# Shield-v1_4.net
KiCad netlist of a schematic drawn in EAGLE
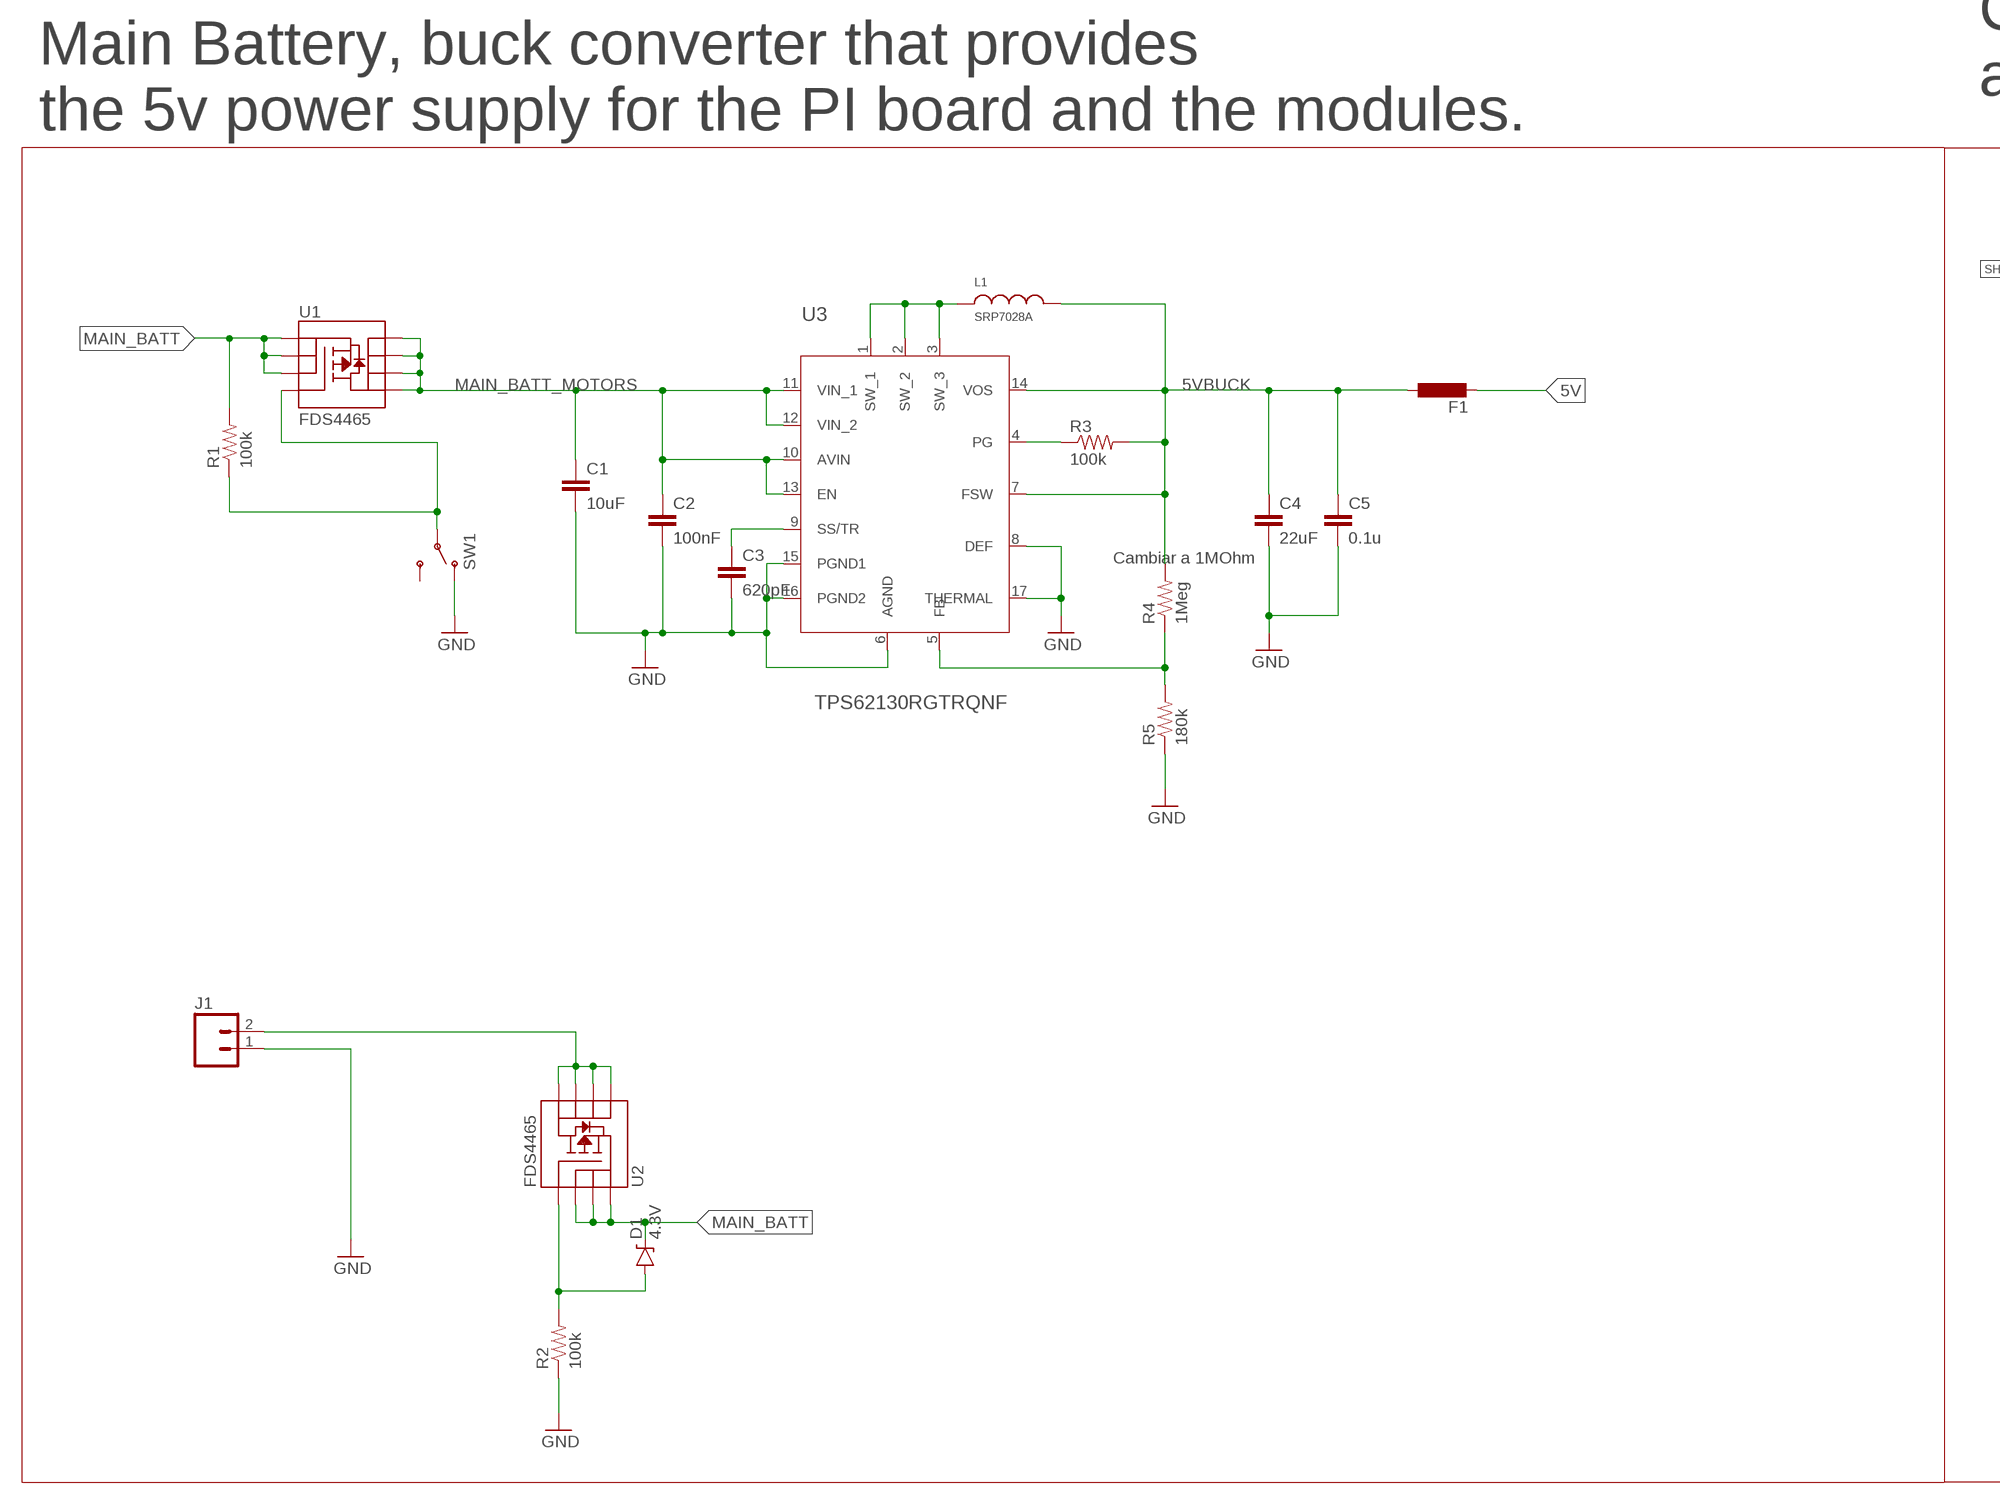
[diagram p0: schematic, sheet 1, part 1 of 2]
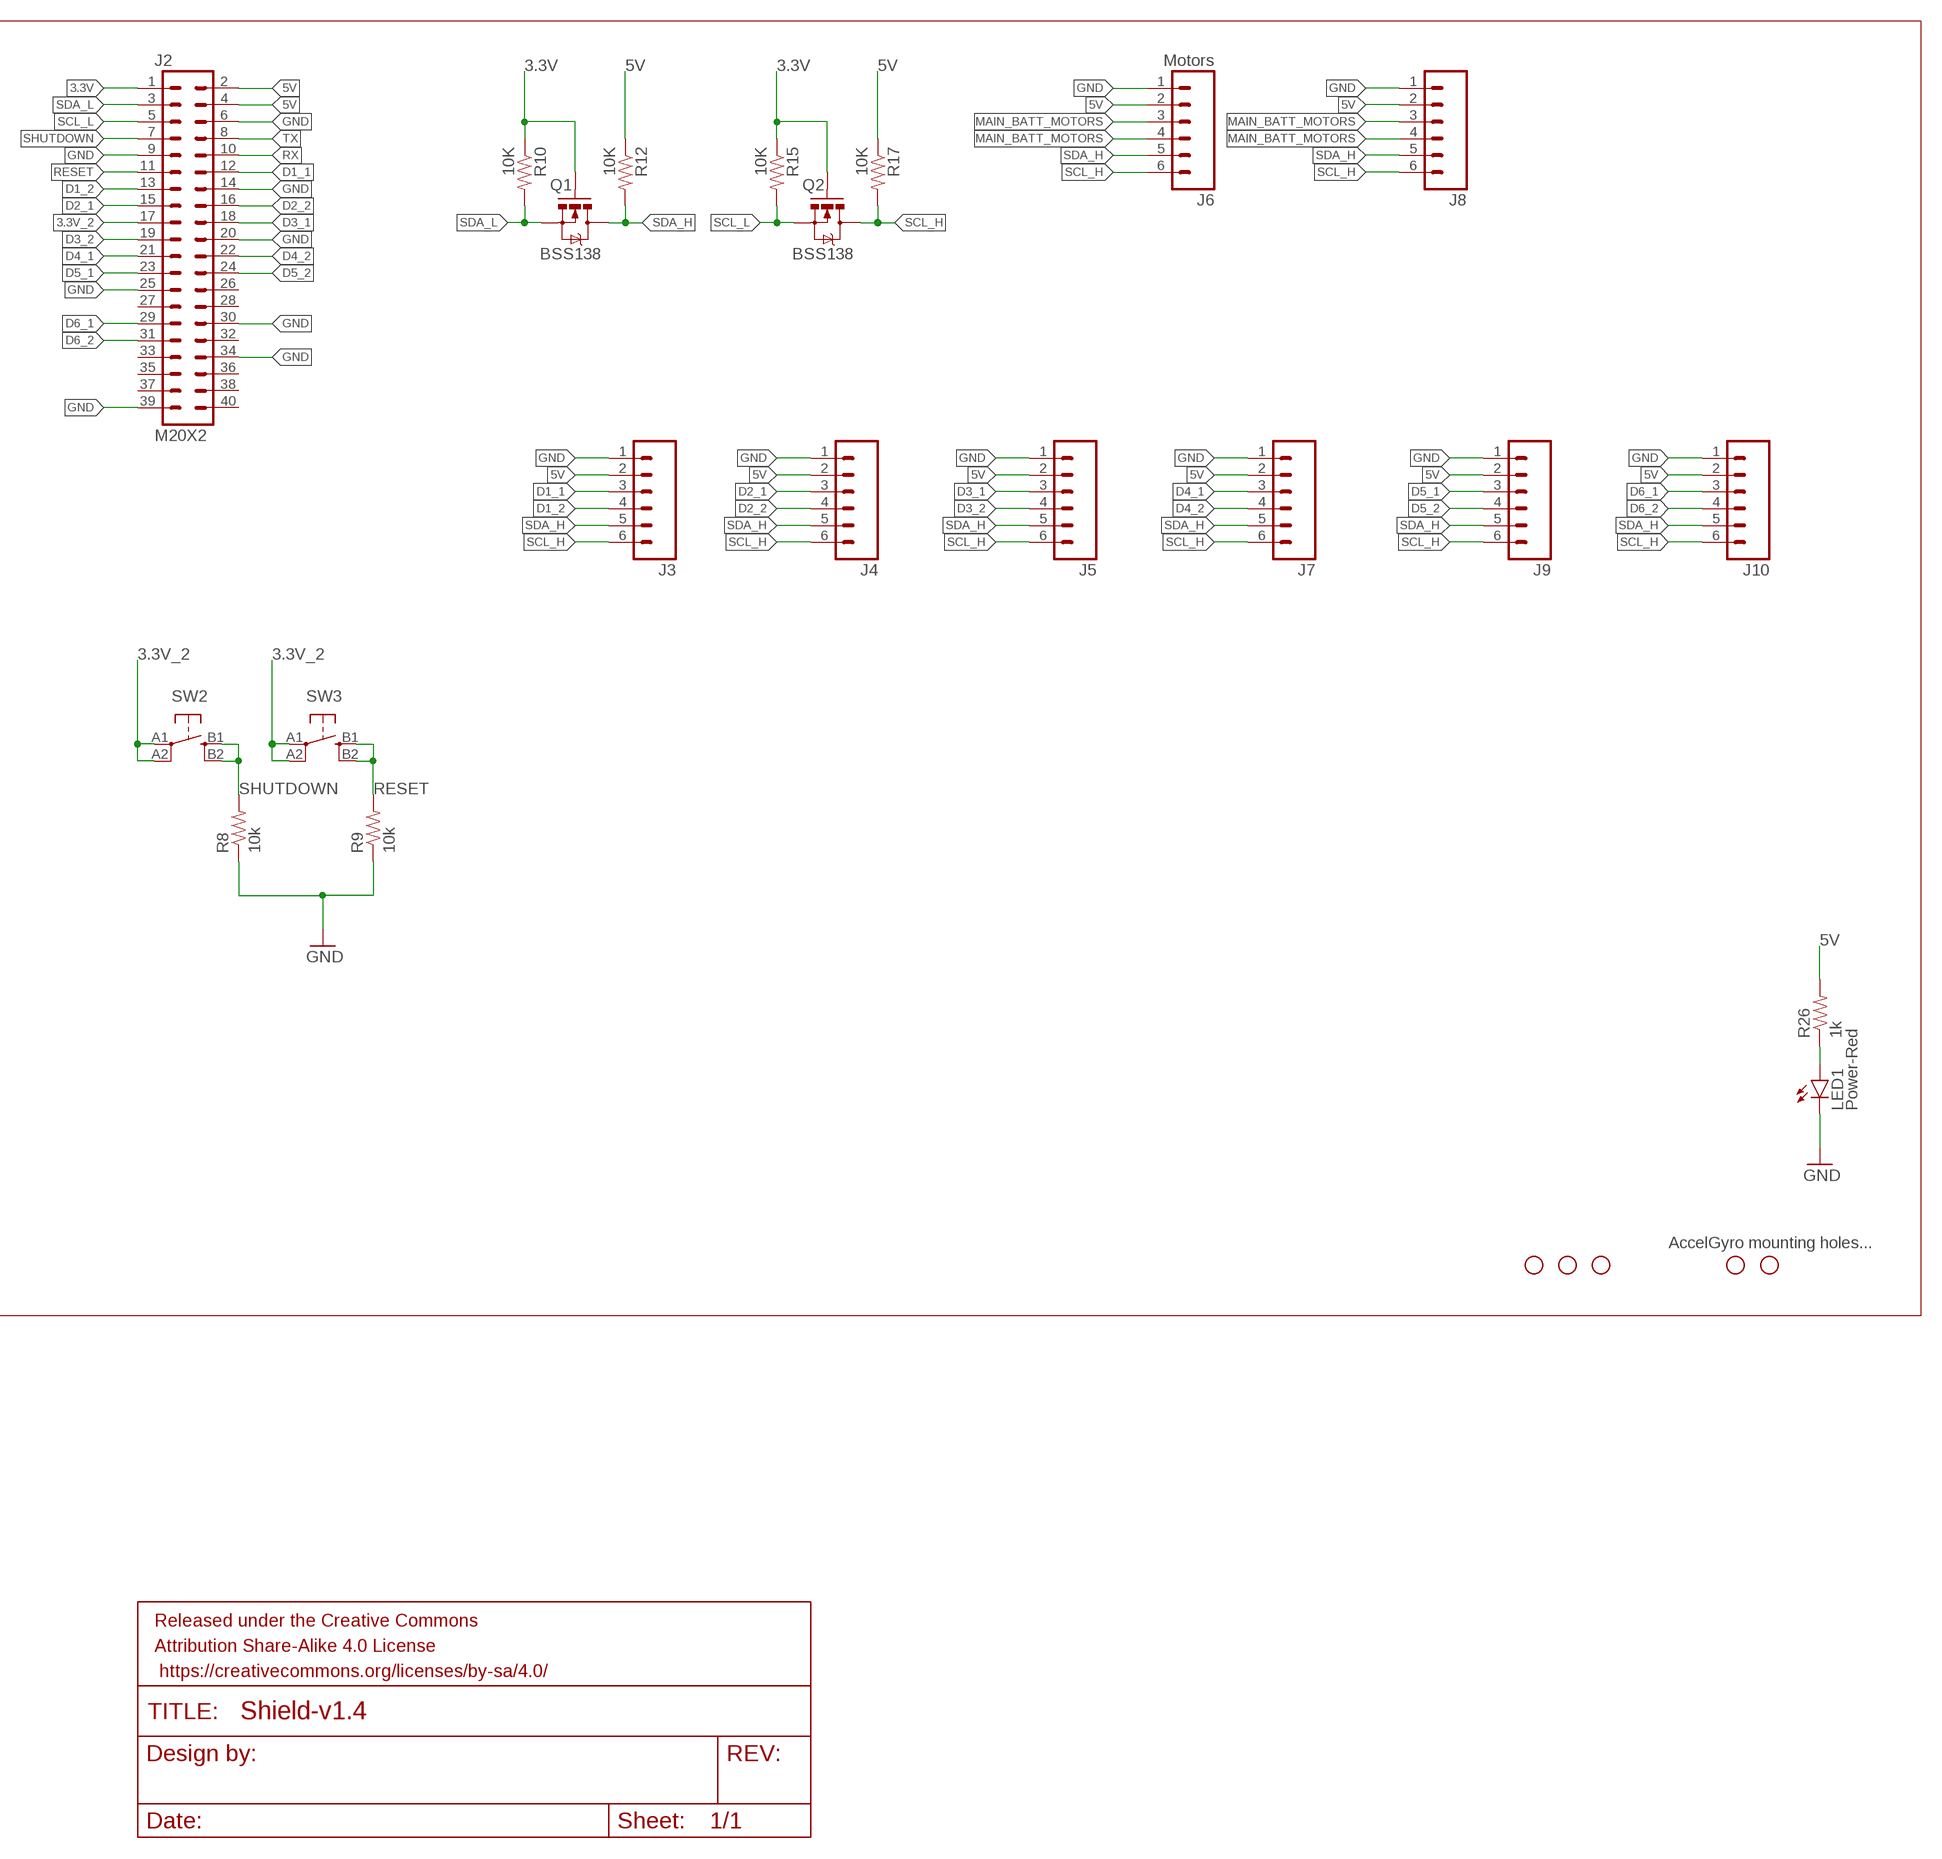
[diagram p1: schematic, sheet 1, part 2 of 2]

(export (version "E")
  (design (tool "Eeschema 10.0.6"))
  (components
    (comp (ref "C1")
      (value "10uF")
      (footprint "eagle-import:0603-CAP")
      (libsource (lib "eagle-import") (part "CAP0603-CAP"))
    )
    (comp (ref "C2")
      (value "100nF")
      (footprint "eagle-import:0603-CAP")
      (libsource (lib "eagle-import") (part "CAP0603-CAP"))
    )
    (comp (ref "C3")
      (value "620pF")
      (footprint "eagle-import:0603-CAP")
      (libsource (lib "eagle-import") (part "CAP0603-CAP"))
    )
    (comp (ref "C4")
      (value "22uF")
      (footprint "eagle-import:0805")
      (libsource (lib "eagle-import") (part "SparkFun-Passives_CAP0805"))
    )
    (comp (ref "C5")
      (value "0.1u")
      (footprint "eagle-import:0603-CAP")
      (libsource (lib "eagle-import") (part "CAP0603-CAP"))
    )
    (comp (ref "D1")
      (value "4.3V")
      (footprint "eagle-import:SOD-323")
      (libsource (lib "eagle-import") (part "DIODE-ZENER3.3V"))
    )
    (comp (ref "F1")
      (value "L-EUL1812")
      (footprint "eagle-import:L1812")
      (libsource (lib "eagle-import") (part "L-EUL1812"))
    )
    (comp (ref "FRAME1")
      (value "FRAME-LETTERNO_PACKAGE")
      (footprint "eagle-import:DUMMY")
      (fields (field (name "DESIGNER") "Nobody"))
      (libsource (lib "eagle-import") (part "FRAME-LETTERNO_PACKAGE"))
    )
    (comp (ref "H1")
      (value "STAND-OFFPLATED")
      (footprint "eagle-import:STAND-OFF-PLATED")
      (libsource (lib "eagle-import") (part "STAND-OFFPLATED"))
    )
    (comp (ref "H2")
      (value "STAND-OFFPLATED")
      (footprint "eagle-import:STAND-OFF-PLATED")
      (libsource (lib "eagle-import") (part "STAND-OFFPLATED"))
    )
    (comp (ref "H3")
      (value "STAND-OFFNORMAL")
      (footprint "eagle-import:STAND-OFF")
      (libsource (lib "eagle-import") (part "STAND-OFFNORMAL"))
    )
    (comp (ref "H4")
      (value "STAND-OFF")
      (footprint "eagle-import:STAND-OFF")
      (libsource (lib "eagle-import") (part "STAND-OFF"))
    )
    (comp (ref "H5")
      (value "STAND-OFF")
      (footprint "eagle-import:STAND-OFF")
      (libsource (lib "eagle-import") (part "STAND-OFF"))
    )
    (comp (ref "J1")
      (value "M02PTH-XH")
      (footprint "eagle-import:JST-2-PTH-XH")
      (libsource (lib "eagle-import") (part "M02PTH-XH"))
    )
    (comp (ref "J2")
      (value "M20X2")
      (footprint "eagle-import:2X20")
      (libsource (lib "eagle-import") (part "M20X2"))
    )
    (comp (ref "J3")
      (value "M06RJ11")
      (footprint "eagle-import:RJ11-6P6C")
      (libsource (lib "eagle-import") (part "M06RJ11"))
    )
    (comp (ref "J4")
      (value "M06RJ11")
      (footprint "eagle-import:RJ11-6P6C")
      (libsource (lib "eagle-import") (part "M06RJ11"))
    )
    (comp (ref "J5")
      (value "M06RJ11")
      (footprint "eagle-import:RJ11-6P6C")
      (libsource (lib "eagle-import") (part "M06RJ11"))
    )
    (comp (ref "J6")
      (value "Motors")
      (footprint "eagle-import:RJ11-6P6C")
      (libsource (lib "eagle-import") (part "M06RJ11"))
    )
    (comp (ref "J7")
      (value "M06RJ11")
      (footprint "eagle-import:RJ11-6P6C")
      (libsource (lib "eagle-import") (part "M06RJ11"))
    )
    (comp (ref "J8")
      (value "M06RJ11")
      (footprint "eagle-import:RJ11-6P6C")
      (libsource (lib "eagle-import") (part "M06RJ11"))
    )
    (comp (ref "J9")
      (value "M06RJ11-SMD")
      (footprint "eagle-import:RJ11-6P6C-SMD")
      (libsource (lib "eagle-import") (part "M06RJ11-SMD"))
    )
    (comp (ref "J10")
      (value "M06RJ11-SMD")
      (footprint "eagle-import:RJ11-6P6C-SMD")
      (libsource (lib "eagle-import") (part "M06RJ11-SMD"))
    )
    (comp (ref "L1")
      (value "SRP7028A")
      (footprint "eagle-import:SRP7028A")
      (libsource (lib "eagle-import") (part "SRP7028A"))
    )
    (comp (ref "LED1")
      (value "Power-Red")
      (footprint "eagle-import:LED-0603")
      (libsource (lib "eagle-import") (part "LED0603"))
    )
    (comp (ref "Q1")
      (value "BSS138")
      (footprint "eagle-import:SOT23-3")
      (libsource (lib "eagle-import") (part "MOSFET-NCHANNELSMD"))
    )
    (comp (ref "Q2")
      (value "BSS138")
      (footprint "eagle-import:SOT23-3")
      (libsource (lib "eagle-import") (part "MOSFET-NCHANNELSMD"))
    )
    (comp (ref "R1")
      (value "100k")
      (footprint "eagle-import:0603-RES")
      (libsource (lib "eagle-import") (part "RESISTOR0603-RES"))
    )
    (comp (ref "R2")
      (value "100k")
      (footprint "eagle-import:0603-RES")
      (libsource (lib "eagle-import") (part "RESISTOR0603-RES"))
    )
    (comp (ref "R3")
      (value "100k")
      (footprint "eagle-import:0603-RES")
      (libsource (lib "eagle-import") (part "RESISTOR0603-RES"))
    )
    (comp (ref "R4")
      (value "1Meg")
      (footprint "eagle-import:0603-RES")
      (libsource (lib "eagle-import") (part "RESISTOR0603-RES"))
    )
    (comp (ref "R5")
      (value "180k")
      (footprint "eagle-import:0603-RES")
      (libsource (lib "eagle-import") (part "RESISTOR0603-RES"))
    )
    (comp (ref "R8")
      (value "10k")
      (footprint "eagle-import:0603-RES")
      (libsource (lib "eagle-import") (part "RESISTOR0603-RES"))
    )
    (comp (ref "R9")
      (value "10k")
      (footprint "eagle-import:0603-RES")
      (libsource (lib "eagle-import") (part "RESISTOR0603-RES"))
    )
    (comp (ref "R10")
      (value "10K")
      (footprint "eagle-import:0603-RES")
      (libsource (lib "eagle-import") (part "RESISTOR0603-RES"))
    )
    (comp (ref "R12")
      (value "10K")
      (footprint "eagle-import:0603-RES")
      (libsource (lib "eagle-import") (part "RESISTOR0603-RES"))
    )
    (comp (ref "R15")
      (value "10K")
      (footprint "eagle-import:0603-RES")
      (libsource (lib "eagle-import") (part "RESISTOR0603-RES"))
    )
    (comp (ref "R17")
      (value "10K")
      (footprint "eagle-import:0603-RES")
      (libsource (lib "eagle-import") (part "RESISTOR0603-RES"))
    )
    (comp (ref "R26")
      (value "1k")
      (footprint "eagle-import:0603-RES")
      (libsource (lib "eagle-import") (part "RESISTOR0603-RES"))
    )
    (comp (ref "SW1")
      (value "SWITCH-SPDT-SPDT-TH")
      (footprint "eagle-import:SW-SPDT-TH")
      (libsource (lib "eagle-import") (part "SWITCH-SPDT-SPDT-TH"))
    )
    (comp (ref "SW2")
      (value "SWITCH_SPST_4_PINTALL")
      (footprint "eagle-import:TACTILE_SWITCH_TALL")
      (libsource (lib "eagle-import") (part "SWITCH_SPST_4_PINTALL"))
    )
    (comp (ref "SW3")
      (value "SWITCH_SPST_4_PINTALL")
      (footprint "eagle-import:TACTILE_SWITCH_TALL")
      (libsource (lib "eagle-import") (part "SWITCH_SPST_4_PINTALL"))
    )
    (comp (ref "U1")
      (value "FDS4465")
      (footprint "eagle-import:SO08")
      (libsource (lib "eagle-import") (part "MOSFET-PCHANNEL-SOIC8SOIC8"))
    )
    (comp (ref "U2")
      (value "FDS4465")
      (footprint "eagle-import:SO08")
      (libsource (lib "eagle-import") (part "MOSFET-PCHANNEL-SOIC8SOIC8"))
    )
    (comp (ref "U3")
      (value "TPS62130RGTRQNF")
      (footprint "eagle-import:QFN-N16")
      (libsource (lib "eagle-import") (part "TPS62130RGTRQNF"))
    )
  )
  (nets
    (net (code "1") (name "/5VBUCK") (class "Default")
      (node (ref "C4") (pin "1") (pinfunction "1_1") (pintype "passive"))
      (node (ref "C5") (pin "1") (pinfunction "1_1") (pintype "passive"))
      (node (ref "F1") (pin "1") (pinfunction "1_1") (pintype "passive"))
      (node (ref "L1") (pin "P$2") (pinfunction "2_P$2") (pintype "bidirectional"))
      (node (ref "R3") (pin "2") (pinfunction "2_2") (pintype "passive"))
      (node (ref "R4") (pin "2") (pinfunction "2_2") (pintype "passive"))
      (node (ref "U3") (pin "14") (pinfunction "VOS_14") (pintype "passive"))
      (node (ref "U3") (pin "7") (pinfunction "FSW_7") (pintype "passive"))
    )
    (net (code "2") (name "3.3V") (class "Default")
      (node (ref "J2") (pin "1") (pinfunction "1_1") (pintype "passive"))
      (node (ref "Q1") (pin "1") (pinfunction "G_1") (pintype "passive"))
      (node (ref "Q2") (pin "1") (pinfunction "G_1") (pintype "passive"))
      (node (ref "R10") (pin "1") (pinfunction "1_1") (pintype "passive"))
      (node (ref "R15") (pin "1") (pinfunction "1_1") (pintype "passive"))
    )
    (net (code "3") (name "3.3V_2") (class "Default")
      (node (ref "J2") (pin "17") (pinfunction "17_17") (pintype "passive"))
      (node (ref "SW2") (pin "A1") (pinfunction "1_A1") (pintype "passive"))
      (node (ref "SW2") (pin "A2") (pinfunction "2_A2") (pintype "passive"))
      (node (ref "SW3") (pin "A1") (pinfunction "1_A1") (pintype "passive"))
      (node (ref "SW3") (pin "A2") (pinfunction "2_A2") (pintype "passive"))
    )
    (net (code "4") (name "5V") (class "Default")
      (node (ref "F1") (pin "2") (pinfunction "2_2") (pintype "passive"))
      (node (ref "J10") (pin "2") (pinfunction "2_2") (pintype "passive"))
      (node (ref "J2") (pin "2") (pinfunction "2_2") (pintype "passive"))
      (node (ref "J2") (pin "4") (pinfunction "4_4") (pintype "passive"))
      (node (ref "J3") (pin "2") (pinfunction "2_2") (pintype "passive"))
      (node (ref "J4") (pin "2") (pinfunction "2_2") (pintype "passive"))
      (node (ref "J5") (pin "2") (pinfunction "2_2") (pintype "passive"))
      (node (ref "J6") (pin "2") (pinfunction "2_2") (pintype "passive"))
      (node (ref "J7") (pin "2") (pinfunction "2_2") (pintype "passive"))
      (node (ref "J8") (pin "2") (pinfunction "2_2") (pintype "passive"))
      (node (ref "J9") (pin "2") (pinfunction "2_2") (pintype "passive"))
      (node (ref "R12") (pin "1") (pinfunction "1_1") (pintype "passive"))
      (node (ref "R17") (pin "1") (pinfunction "1_1") (pintype "passive"))
      (node (ref "R26") (pin "2") (pinfunction "2_2") (pintype "passive"))
    )
    (net (code "5") (name "D1_1") (class "Default")
      (node (ref "J2") (pin "12") (pinfunction "12_12") (pintype "passive"))
      (node (ref "J3") (pin "3") (pinfunction "3_3") (pintype "passive"))
    )
    (net (code "6") (name "D1_2") (class "Default")
      (node (ref "J2") (pin "13") (pinfunction "13_13") (pintype "passive"))
      (node (ref "J3") (pin "4") (pinfunction "4_4") (pintype "passive"))
    )
    (net (code "7") (name "D2_1") (class "Default")
      (node (ref "J2") (pin "15") (pinfunction "15_15") (pintype "passive"))
      (node (ref "J4") (pin "3") (pinfunction "3_3") (pintype "passive"))
    )
    (net (code "8") (name "D2_2") (class "Default")
      (node (ref "J2") (pin "16") (pinfunction "16_16") (pintype "passive"))
      (node (ref "J4") (pin "4") (pinfunction "4_4") (pintype "passive"))
    )
    (net (code "9") (name "D3_1") (class "Default")
      (node (ref "J2") (pin "18") (pinfunction "18_18") (pintype "passive"))
      (node (ref "J5") (pin "3") (pinfunction "3_3") (pintype "passive"))
    )
    (net (code "10") (name "D3_2") (class "Default")
      (node (ref "J2") (pin "19") (pinfunction "19_19") (pintype "passive"))
      (node (ref "J5") (pin "4") (pinfunction "4_4") (pintype "passive"))
    )
    (net (code "11") (name "D4_1") (class "Default")
      (node (ref "J2") (pin "21") (pinfunction "21_21") (pintype "passive"))
      (node (ref "J7") (pin "3") (pinfunction "3_3") (pintype "passive"))
    )
    (net (code "12") (name "D4_2") (class "Default")
      (node (ref "J2") (pin "22") (pinfunction "22_22") (pintype "passive"))
      (node (ref "J7") (pin "4") (pinfunction "4_4") (pintype "passive"))
    )
    (net (code "13") (name "D5_1") (class "Default")
      (node (ref "J2") (pin "23") (pinfunction "23_23") (pintype "passive"))
      (node (ref "J9") (pin "3") (pinfunction "3_3") (pintype "passive"))
    )
    (net (code "14") (name "D5_2") (class "Default")
      (node (ref "J2") (pin "24") (pinfunction "24_24") (pintype "passive"))
      (node (ref "J9") (pin "4") (pinfunction "4_4") (pintype "passive"))
    )
    (net (code "15") (name "D6_1") (class "Default")
      (node (ref "J10") (pin "3") (pinfunction "3_3") (pintype "passive"))
      (node (ref "J2") (pin "29") (pinfunction "29_29") (pintype "passive"))
    )
    (net (code "16") (name "D6_2") (class "Default")
      (node (ref "J10") (pin "4") (pinfunction "4_4") (pintype "passive"))
      (node (ref "J2") (pin "31") (pinfunction "31_31") (pintype "passive"))
    )
    (net (code "17") (name "GND") (class "Default")
      (node (ref "C1") (pin "2") (pinfunction "2_2") (pintype "passive"))
      (node (ref "C2") (pin "2") (pinfunction "2_2") (pintype "passive"))
      (node (ref "C3") (pin "2") (pinfunction "2_2") (pintype "passive"))
      (node (ref "C4") (pin "2") (pinfunction "2_2") (pintype "passive"))
      (node (ref "C5") (pin "2") (pinfunction "2_2") (pintype "passive"))
      (node (ref "J1") (pin "1") (pinfunction "1_1") (pintype "passive"))
      (node (ref "J10") (pin "1") (pinfunction "1_1") (pintype "passive"))
      (node (ref "J2") (pin "14") (pinfunction "14_14") (pintype "passive"))
      (node (ref "J2") (pin "20") (pinfunction "20_20") (pintype "passive"))
      (node (ref "J2") (pin "25") (pinfunction "25_25") (pintype "passive"))
      (node (ref "J2") (pin "30") (pinfunction "30_30") (pintype "passive"))
      (node (ref "J2") (pin "34") (pinfunction "34_34") (pintype "passive"))
      (node (ref "J2") (pin "39") (pinfunction "39_39") (pintype "passive"))
      (node (ref "J2") (pin "6") (pinfunction "6_6") (pintype "passive"))
      (node (ref "J2") (pin "9") (pinfunction "9_9") (pintype "passive"))
      (node (ref "J3") (pin "1") (pinfunction "1_1") (pintype "passive"))
      (node (ref "J4") (pin "1") (pinfunction "1_1") (pintype "passive"))
      (node (ref "J5") (pin "1") (pinfunction "1_1") (pintype "passive"))
      (node (ref "J6") (pin "1") (pinfunction "1_1") (pintype "passive"))
      (node (ref "J7") (pin "1") (pinfunction "1_1") (pintype "passive"))
      (node (ref "J8") (pin "1") (pinfunction "1_1") (pintype "passive"))
      (node (ref "J9") (pin "1") (pinfunction "1_1") (pintype "passive"))
      (node (ref "LED1") (pin "C") (pinfunction "C_C") (pintype "passive"))
      (node (ref "R2") (pin "1") (pinfunction "1_1") (pintype "passive"))
      (node (ref "R5") (pin "1") (pinfunction "1_1") (pintype "passive"))
      (node (ref "R8") (pin "1") (pinfunction "1_1") (pintype "passive"))
      (node (ref "R9") (pin "1") (pinfunction "1_1") (pintype "passive"))
      (node (ref "SW1") (pin "P$3") (pinfunction "O_P$3") (pintype "passive"))
      (node (ref "U3") (pin "15") (pinfunction "PGND1_15") (pintype "passive"))
      (node (ref "U3") (pin "16") (pinfunction "PGND2_16") (pintype "bidirectional"))
      (node (ref "U3") (pin "17") (pinfunction "THERMAL_17") (pintype "bidirectional"))
      (node (ref "U3") (pin "6") (pinfunction "AGND_6") (pintype "passive"))
      (node (ref "U3") (pin "8") (pinfunction "DEF_8") (pintype "passive"))
    )
    (net (code "18") (name "MAIN_BATT") (class "Default")
      (node (ref "D1") (pin "C") (pinfunction "C_C") (pintype "passive"))
      (node (ref "R1") (pin "2") (pinfunction "2_2") (pintype "passive"))
      (node (ref "U1") (pin "1") (pinfunction "S_1") (pintype "bidirectional"))
      (node (ref "U1") (pin "2") (pinfunction "S_2") (pintype "bidirectional"))
      (node (ref "U1") (pin "3") (pinfunction "S_3") (pintype "bidirectional"))
      (node (ref "U2") (pin "1") (pinfunction "S_1") (pintype "bidirectional"))
      (node (ref "U2") (pin "2") (pinfunction "S_2") (pintype "bidirectional"))
      (node (ref "U2") (pin "3") (pinfunction "S_3") (pintype "bidirectional"))
    )
    (net (code "19") (name "MAIN_BATT_MOTORS") (class "Default")
      (node (ref "C1") (pin "1") (pinfunction "1_1") (pintype "passive"))
      (node (ref "C2") (pin "1") (pinfunction "1_1") (pintype "passive"))
      (node (ref "J6") (pin "3") (pinfunction "3_3") (pintype "passive"))
      (node (ref "J6") (pin "4") (pinfunction "4_4") (pintype "passive"))
      (node (ref "J8") (pin "3") (pinfunction "3_3") (pintype "passive"))
      (node (ref "J8") (pin "4") (pinfunction "4_4") (pintype "passive"))
      (node (ref "U1") (pin "5") (pinfunction "D_5") (pintype "bidirectional"))
      (node (ref "U1") (pin "6") (pinfunction "D_6") (pintype "bidirectional"))
      (node (ref "U1") (pin "7") (pinfunction "D_7") (pintype "bidirectional"))
      (node (ref "U1") (pin "8") (pinfunction "D_8") (pintype "bidirectional"))
      (node (ref "U3") (pin "10") (pinfunction "AVIN_10") (pintype "passive"))
      (node (ref "U3") (pin "11") (pinfunction "VIN_1_11") (pintype "passive"))
      (node (ref "U3") (pin "12") (pinfunction "VIN_2_12") (pintype "passive"))
      (node (ref "U3") (pin "13") (pinfunction "EN_13") (pintype "passive"))
    )
    (net (code "20") (name "Net-(J1-Pad2)") (class "Default")
      (node (ref "J1") (pin "2") (pinfunction "2_2") (pintype "passive"))
      (node (ref "U2") (pin "5") (pinfunction "D_5") (pintype "bidirectional"))
      (node (ref "U2") (pin "6") (pinfunction "D_6") (pintype "bidirectional"))
      (node (ref "U2") (pin "7") (pinfunction "D_7") (pintype "bidirectional"))
      (node (ref "U2") (pin "8") (pinfunction "D_8") (pintype "bidirectional"))
    )
    (net (code "21") (name "Net-(L1-1)") (class "Default")
      (node (ref "L1") (pin "P$1") (pinfunction "1_P$1") (pintype "bidirectional"))
      (node (ref "U3") (pin "1") (pinfunction "SW_1_1") (pintype "passive"))
      (node (ref "U3") (pin "2") (pinfunction "SW_2_2") (pintype "passive"))
      (node (ref "U3") (pin "3") (pinfunction "SW_3_3") (pintype "passive"))
    )
    (net (code "22") (name "Net-(LED1-PadA)") (class "Default")
      (node (ref "LED1") (pin "A") (pinfunction "A_A") (pintype "passive"))
      (node (ref "R26") (pin "1") (pinfunction "1_1") (pintype "passive"))
    )
    (net (code "23") (name "Net-(SW1-P)") (class "Default")
      (node (ref "R1") (pin "1") (pinfunction "1_1") (pintype "passive"))
      (node (ref "SW1") (pin "P$2") (pinfunction "P_P$2") (pintype "passive"))
      (node (ref "U1") (pin "4") (pinfunction "G_4") (pintype "bidirectional"))
    )
    (net (code "24") (name "Net-(U2-G)") (class "Default")
      (node (ref "D1") (pin "A") (pinfunction "A_A") (pintype "passive"))
      (node (ref "R2") (pin "2") (pinfunction "2_2") (pintype "passive"))
      (node (ref "U2") (pin "4") (pinfunction "G_4") (pintype "bidirectional"))
    )
    (net (code "25") (name "Net-(U3-FB)") (class "Default")
      (node (ref "R4") (pin "1") (pinfunction "1_1") (pintype "passive"))
      (node (ref "R5") (pin "2") (pinfunction "2_2") (pintype "passive"))
      (node (ref "U3") (pin "5") (pinfunction "FB_5") (pintype "passive"))
    )
    (net (code "26") (name "Net-(U3-PG)") (class "Default")
      (node (ref "R3") (pin "1") (pinfunction "1_1") (pintype "passive"))
      (node (ref "U3") (pin "4") (pinfunction "PG_4") (pintype "passive"))
    )
    (net (code "27") (name "Net-(U3-SS{slash}TR)") (class "Default")
      (node (ref "C3") (pin "1") (pinfunction "1_1") (pintype "passive"))
      (node (ref "U3") (pin "9") (pinfunction "SS/TR_9") (pintype "passive"))
    )
    (net (code "28") (name "RESET") (class "Default")
      (node (ref "J2") (pin "11") (pinfunction "11_11") (pintype "passive"))
      (node (ref "R9") (pin "2") (pinfunction "2_2") (pintype "passive"))
      (node (ref "SW3") (pin "B1") (pinfunction "3_B1") (pintype "passive"))
      (node (ref "SW3") (pin "B2") (pinfunction "4_B2") (pintype "passive"))
    )
    (net (code "29") (name "RX") (class "Default")
      (node (ref "J2") (pin "10") (pinfunction "10_10") (pintype "passive"))
    )
    (net (code "30") (name "SCL_H") (class "Default")
      (node (ref "J10") (pin "6") (pinfunction "6_6") (pintype "passive"))
      (node (ref "J3") (pin "6") (pinfunction "6_6") (pintype "passive"))
      (node (ref "J4") (pin "6") (pinfunction "6_6") (pintype "passive"))
      (node (ref "J5") (pin "6") (pinfunction "6_6") (pintype "passive"))
      (node (ref "J6") (pin "6") (pinfunction "6_6") (pintype "passive"))
      (node (ref "J7") (pin "6") (pinfunction "6_6") (pintype "passive"))
      (node (ref "J8") (pin "6") (pinfunction "6_6") (pintype "passive"))
      (node (ref "J9") (pin "6") (pinfunction "6_6") (pintype "passive"))
      (node (ref "Q2") (pin "3") (pinfunction "D_3") (pintype "passive"))
      (node (ref "R17") (pin "2") (pinfunction "2_2") (pintype "passive"))
    )
    (net (code "31") (name "SCL_L") (class "Default")
      (node (ref "J2") (pin "5") (pinfunction "5_5") (pintype "passive"))
      (node (ref "Q2") (pin "2") (pinfunction "S_2") (pintype "passive"))
      (node (ref "R15") (pin "2") (pinfunction "2_2") (pintype "passive"))
    )
    (net (code "32") (name "SDA_H") (class "Default")
      (node (ref "J10") (pin "5") (pinfunction "5_5") (pintype "passive"))
      (node (ref "J3") (pin "5") (pinfunction "5_5") (pintype "passive"))
      (node (ref "J4") (pin "5") (pinfunction "5_5") (pintype "passive"))
      (node (ref "J5") (pin "5") (pinfunction "5_5") (pintype "passive"))
      (node (ref "J6") (pin "5") (pinfunction "5_5") (pintype "passive"))
      (node (ref "J7") (pin "5") (pinfunction "5_5") (pintype "passive"))
      (node (ref "J8") (pin "5") (pinfunction "5_5") (pintype "passive"))
      (node (ref "J9") (pin "5") (pinfunction "5_5") (pintype "passive"))
      (node (ref "Q1") (pin "3") (pinfunction "D_3") (pintype "passive"))
      (node (ref "R12") (pin "2") (pinfunction "2_2") (pintype "passive"))
    )
    (net (code "33") (name "SDA_L") (class "Default")
      (node (ref "J2") (pin "3") (pinfunction "3_3") (pintype "passive"))
      (node (ref "Q1") (pin "2") (pinfunction "S_2") (pintype "passive"))
      (node (ref "R10") (pin "2") (pinfunction "2_2") (pintype "passive"))
    )
    (net (code "34") (name "SHUTDOWN") (class "Default")
      (node (ref "J2") (pin "7") (pinfunction "7_7") (pintype "passive"))
      (node (ref "R8") (pin "2") (pinfunction "2_2") (pintype "passive"))
      (node (ref "SW2") (pin "B1") (pinfunction "3_B1") (pintype "passive"))
      (node (ref "SW2") (pin "B2") (pinfunction "4_B2") (pintype "passive"))
    )
    (net (code "35") (name "TX") (class "Default")
      (node (ref "J2") (pin "8") (pinfunction "8_8") (pintype "passive"))
    )
    (net (code "36") (name "unconnected-(J2-Pad26)") (class "Default")
      (node (ref "J2") (pin "26") (pinfunction "26_26") (pintype "passive"))
    )
    (net (code "37") (name "unconnected-(J2-Pad27)") (class "Default")
      (node (ref "J2") (pin "27") (pinfunction "27_27") (pintype "passive"))
    )
    (net (code "38") (name "unconnected-(J2-Pad28)") (class "Default")
      (node (ref "J2") (pin "28") (pinfunction "28_28") (pintype "passive"))
    )
    (net (code "39") (name "unconnected-(J2-Pad32)") (class "Default")
      (node (ref "J2") (pin "32") (pinfunction "32_32") (pintype "passive"))
    )
    (net (code "40") (name "unconnected-(J2-Pad33)") (class "Default")
      (node (ref "J2") (pin "33") (pinfunction "33_33") (pintype "passive"))
    )
    (net (code "41") (name "unconnected-(J2-Pad35)") (class "Default")
      (node (ref "J2") (pin "35") (pinfunction "35_35") (pintype "passive"))
    )
    (net (code "42") (name "unconnected-(J2-Pad36)") (class "Default")
      (node (ref "J2") (pin "36") (pinfunction "36_36") (pintype "passive"))
    )
    (net (code "43") (name "unconnected-(J2-Pad37)") (class "Default")
      (node (ref "J2") (pin "37") (pinfunction "37_37") (pintype "passive"))
    )
    (net (code "44") (name "unconnected-(J2-Pad38)") (class "Default")
      (node (ref "J2") (pin "38") (pinfunction "38_38") (pintype "passive"))
    )
    (net (code "45") (name "unconnected-(J2-Pad40)") (class "Default")
      (node (ref "J2") (pin "40") (pinfunction "40_40") (pintype "passive"))
    )
    (net (code "46") (name "unconnected-(SW1-S-PadP$1)") (class "Default")
      (node (ref "SW1") (pin "P$1") (pinfunction "S_P$1") (pintype "passive"))
    )
  )
)
